# 1_P1.net
KiCad netlist of a schematic drawn in Altium Designer
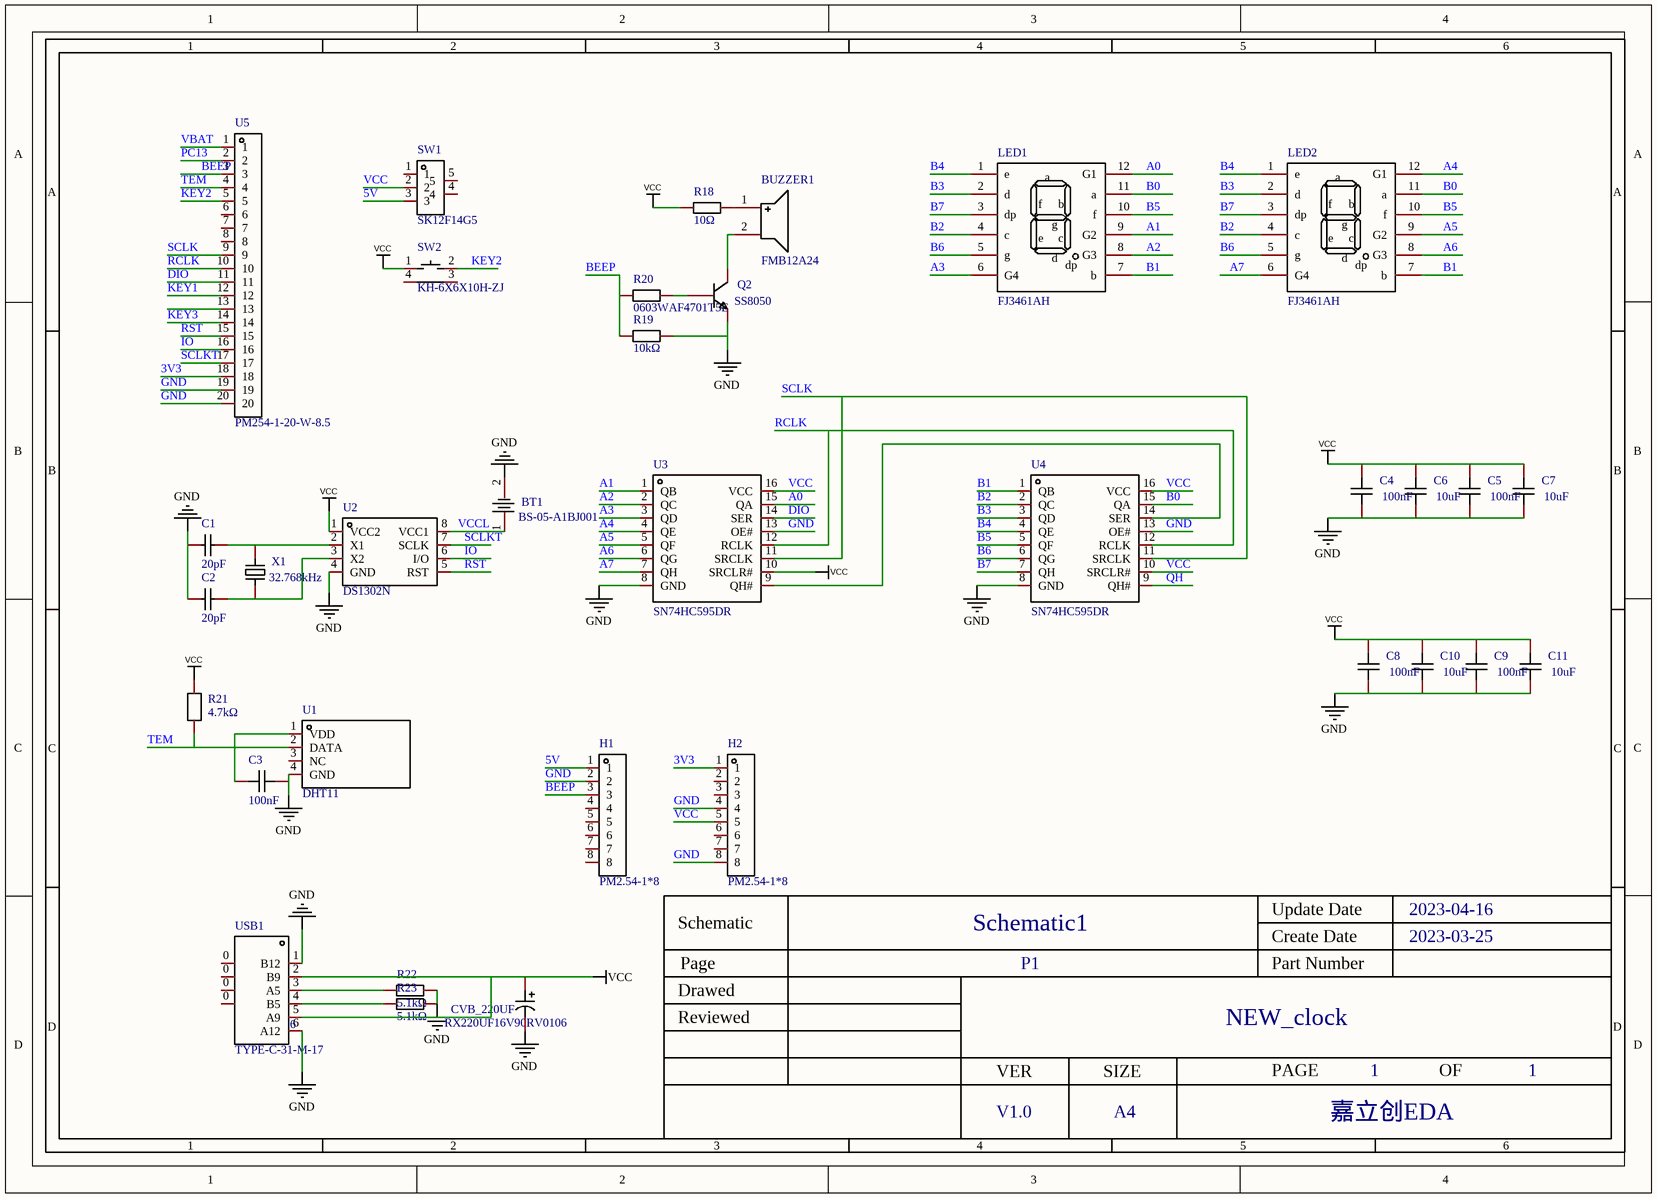
[diagram p0: 1_P1.schdoc]

(export (version "E")
  (design (tool "Eeschema 10.0.6"))
  (components
    (comp (ref "BT1")
      (value "BS-05-A1BJ001")
      (description "连接器类型:电池底座;适用电池规格:CR2032;工作温度范围:-25℃~+85℃;")
      (fields (field (name "NAME") "BS-05-A1BJ001") (field (name "MANUFACTURER") "MYOUNG(美阳)"))
      (libsource (lib "altium-import") (part "root_1_BS-05-A1BJ001_"))
    )
    (comp (ref "BUZZER1")
      (value "FMB12A24")
      (fields (field (name "NAME") "FMB12A24") (field (name "MANUFACTURER") "FUET(福声科技)"))
      (libsource (lib "altium-import") (part "root_0_FMB12A24_"))
    )
    (comp (ref "C1")
      (value "20pF")
      (description "容值:20pF;精度:±5%;额定电压:50V;材质(温度系数):C0G;")
      (fields
        (field (name "NAME") "20pF")
        (field (name "MANUFACTURER") "SAMSUNG(三星)")
        (field (name "MANUFACTURER PART") "CL10C200JB8NNNC")
      )
      (libsource (lib "altium-import") (part "root_0_CL10C200JB8NNNC_"))
    )
    (comp (ref "C2")
      (value "20pF")
      (description "容值:20pF;精度:±5%;额定电压:50V;材质(温度系数):C0G;")
      (fields
        (field (name "NAME") "20pF")
        (field (name "MANUFACTURER") "SAMSUNG(三星)")
        (field (name "MANUFACTURER PART") "CL10C200JB8NNNC")
      )
      (libsource (lib "altium-import") (part "root_0_CL10C200JB8NNNC_"))
    )
    (comp (ref "C3")
      (value "100nF")
      (description "容值:100nF;精度:±10%;额定电压:50V;材质(温度系数):X7R;")
      (fields
        (field (name "NAME") "100nF")
        (field (name "MANUFACTURER") "SAMSUNG(三星)")
        (field (name "MANUFACTURER PART") "CL10B104KB8NNNC")
      )
      (libsource (lib "altium-import") (part "root_0_CL10B104KB8NNNC_"))
    )
    (comp (ref "C4")
      (value "100nF")
      (description "容值:100nF;精度:±10%;额定电压:50V;材质(温度系数):X7R;")
      (fields
        (field (name "NAME") "100nF")
        (field (name "MANUFACTURER") "SAMSUNG(三星)")
        (field (name "MANUFACTURER PART") "CL10B104KB8NNNC")
      )
      (libsource (lib "altium-import") (part "root_1_CL10B104KB8NNNC_"))
    )
    (comp (ref "C5")
      (value "100nF")
      (description "容值:100nF;精度:±10%;额定电压:50V;材质(温度系数):X7R;")
      (fields
        (field (name "NAME") "100nF")
        (field (name "MANUFACTURER") "SAMSUNG(三星)")
        (field (name "MANUFACTURER PART") "CL10B104KB8NNNC")
      )
      (libsource (lib "altium-import") (part "root_1_CL10B104KB8NNNC_"))
    )
    (comp (ref "C6")
      (value "10uF")
      (description "容值:10uF;精度:±20%;额定电压:25V;材质(温度系数):X5R;")
      (fields
        (field (name "NAME") "10uF")
        (field (name "MANUFACTURER") "SAMSUNG(三星)")
        (field (name "MANUFACTURER PART") "CL10A106MA8NRNC")
      )
      (libsource (lib "altium-import") (part "root_1_CL10A106MA8NRNC_"))
    )
    (comp (ref "C7")
      (value "10uF")
      (description "容值:10uF;精度:±20%;额定电压:25V;材质(温度系数):X5R;")
      (fields
        (field (name "NAME") "10uF")
        (field (name "MANUFACTURER") "SAMSUNG(三星)")
        (field (name "MANUFACTURER PART") "CL10A106MA8NRNC")
      )
      (libsource (lib "altium-import") (part "root_1_CL10A106MA8NRNC_"))
    )
    (comp (ref "C8")
      (value "100nF")
      (description "容值:100nF;精度:±10%;额定电压:50V;材质(温度系数):X7R;")
      (fields
        (field (name "NAME") "100nF")
        (field (name "MANUFACTURER") "SAMSUNG(三星)")
        (field (name "MANUFACTURER PART") "CL10B104KB8NNNC")
      )
      (libsource (lib "altium-import") (part "root_1_CL10B104KB8NNNC_"))
    )
    (comp (ref "C9")
      (value "100nF")
      (description "容值:100nF;精度:±10%;额定电压:50V;材质(温度系数):X7R;")
      (fields
        (field (name "NAME") "100nF")
        (field (name "MANUFACTURER") "SAMSUNG(三星)")
        (field (name "MANUFACTURER PART") "CL10B104KB8NNNC")
      )
      (libsource (lib "altium-import") (part "root_1_CL10B104KB8NNNC_"))
    )
    (comp (ref "C10")
      (value "10uF")
      (description "容值:10uF;精度:±20%;额定电压:25V;材质(温度系数):X5R;")
      (fields
        (field (name "NAME") "10uF")
        (field (name "MANUFACTURER") "SAMSUNG(三星)")
        (field (name "MANUFACTURER PART") "CL10A106MA8NRNC")
      )
      (libsource (lib "altium-import") (part "root_1_CL10A106MA8NRNC_"))
    )
    (comp (ref "C11")
      (value "10uF")
      (description "容值:10uF;精度:±20%;额定电压:25V;材质(温度系数):X5R;")
      (fields
        (field (name "NAME") "10uF")
        (field (name "MANUFACTURER") "SAMSUNG(三星)")
        (field (name "MANUFACTURER PART") "CL10A106MA8NRNC")
      )
      (libsource (lib "altium-import") (part "root_1_CL10A106MA8NRNC_"))
    )
    (comp (ref "CVB_220UF")
      (value "RX220UF16V90RV0106")
      (description "RX系列小型化极低阻抗系列贴片电解电容器 105℃2000小时")
      (fields (field (name "NAME") "RX220UF16V90RV0106") (field (name "MANUFACTURER") "KNSCHA(科尼盛)"))
      (libsource (lib "altium-import") (part "root_3_RX220UF16V90RV0106_"))
    )
    (comp (ref "H1")
      (value "PM2.54-1*8")
      (fields (field (name "NAME") "PM2.54-1*8") (field (name "MANUFACTURER") "ZHOURI(洲日)"))
      (libsource (lib "altium-import") (part "root_0_PM2.54-1*8_"))
    )
    (comp (ref "H2")
      (value "PM2.54-1*8")
      (fields (field (name "NAME") "PM2.54-1*8") (field (name "MANUFACTURER") "ZHOURI(洲日)"))
      (libsource (lib "altium-import") (part "root_0_PM2.54-1*8_"))
    )
    (comp (ref "LED1")
      (value "FJ3461AH")
      (description "数字/字母大小(英寸):0.36;发光颜色:红色;")
      (fields (field (name "NAME") "FJ3461AH") (field (name "MANUFACTURER") "志浩"))
      (libsource (lib "altium-import") (part "root_0_FJ3461AH_"))
    )
    (comp (ref "LED2")
      (value "FJ3461AH")
      (description "数字/字母大小(英寸):0.36;发光颜色:红色;")
      (fields (field (name "NAME") "FJ3461AH") (field (name "MANUFACTURER") "志浩"))
      (libsource (lib "altium-import") (part "root_0_FJ3461AH_"))
    )
    (comp (ref "Q2")
      (value "SS8050")
      (fields (field (name "NAME") "SS8050") (field (name "MANUFACTURER") "CJ(江苏长电/长晶)"))
      (libsource (lib "altium-import") (part "root_0_SS8050_C177739_"))
    )
    (comp (ref "R18")
      (value "10Ω")
      (description "电阻类型:厚膜电阻;阻值:10Ω;精度:±5%;功率:100mW;温度系数:±100ppm/℃;最大工作电压:75V;工作温度范围:-55℃~+155℃;")
      (fields
        (field (name "NAME") "10Ω")
        (field (name "MANUFACTURER") "RALEC(旺诠)")
        (field (name "MANUFACTURER PART") "RTT03100JTP")
      )
      (libsource (lib "altium-import") (part "root_0_RTT03100JTP_"))
    )
    (comp (ref "R19")
      (value "10kΩ")
      (description "电阻类型:厚膜电阻;阻值:10kΩ;精度:±1%;功率:100mW;温度系数:±100ppm/℃;最大工作电压:75V;工作温度范围:-55℃~+155℃;")
      (fields
        (field (name "NAME") "10kΩ")
        (field (name "MANUFACTURER") "UNI-ROYAL(厚声)")
        (field (name "MANUFACTURER PART") "0603WAF1002T5E")
      )
      (libsource (lib "altium-import") (part "root_0_0603WAF1002T5E_"))
    )
    (comp (ref "R20")
      (value "0603WAF4701T5E")
      (fields (field (name "NAME") "0603WAF4701T5E") (field (name "MANUFACTURER") "UNI-ROYAL(厚声)"))
      (libsource (lib "altium-import") (part "root_0_0603WAF4701T5E_"))
    )
    (comp (ref "R21")
      (value "4.7kΩ")
      (description "电阻类型:厚膜电阻;阻值:4.7kΩ;精度:±5%;功率:100mW;温度系数:±200ppm/℃;最大工作电压:-;工作温度范围:-55℃~+155℃;")
      (fields
        (field (name "NAME") "4.7kΩ")
        (field (name "MANUFACTURER") "PANASONIC(松下)")
        (field (name "MANUFACTURER PART") "ERJ3GEYJ472V")
      )
      (libsource (lib "altium-import") (part "root_1_ERJ3GEYJ472V_"))
    )
    (comp (ref "R22")
      (value "5.1kΩ")
      (description "电阻类型:厚膜电阻;阻值:5.1kΩ;精度:±1%;功率:100mW;温度系数:±100ppm/℃;最大工作电压:75V;工作温度范围:-55℃~+155℃;")
      (fields
        (field (name "NAME") "5.1kΩ")
        (field (name "MANUFACTURER") "UNI-ROYAL(厚声)")
        (field (name "MANUFACTURER PART") "0603WAF5101T5E")
      )
      (libsource (lib "altium-import") (part "root_0_0603WAF5101T5E_"))
    )
    (comp (ref "R23")
      (value "5.1kΩ")
      (description "电阻类型:厚膜电阻;阻值:5.1kΩ;精度:±1%;功率:100mW;温度系数:±100ppm/℃;最大工作电压:75V;工作温度范围:-55℃~+155℃;")
      (fields
        (field (name "NAME") "5.1kΩ")
        (field (name "MANUFACTURER") "UNI-ROYAL(厚声)")
        (field (name "MANUFACTURER PART") "0603WAF5101T5E")
      )
      (libsource (lib "altium-import") (part "root_0_0603WAF5101T5E_"))
    )
    (comp (ref "SW1")
      (value "SK12F14G5")
      (fields (field (name "NAME") "SK12F14G5") (field (name "MANUFACTURER") "SHOU HAN(首韩)"))
      (libsource (lib "altium-import") (part "root_0_SK12F14G5_"))
    )
    (comp (ref "SW2")
      (value "KH-6X6X10H-ZJ")
      (fields (field (name "NAME") "KH-6X6X10H-ZJ") (field (name "MANUFACTURER") "kinghelm(金航标)"))
      (libsource (lib "altium-import") (part "root_0_KH-6X6X10H-ZJ_"))
    )
    (comp (ref "U1")
      (value "DHT11")
      (description "新款电容式数字温湿度传感器,老款已停产16.1x12.6x5.8mm")
      (fields (field (name "NAME") "DHT11") (field (name "MANUFACTURER") "广州奥松"))
      (libsource (lib "altium-import") (part "root_0_DHT11_"))
    )
    (comp (ref "U2")
      (value "DS1302N")
      (fields (field (name "NAME") "DS1302N") (field (name "MANUFACTURER") "HGSEMI(华冠)"))
      (libsource (lib "altium-import") (part "root_0_DS1302N_"))
    )
    (comp (ref "U3")
      (value "SN74HC595DR")
      (description "逻辑电路的归属系列:74HC;逻辑类型:移位寄存器;输出类型:三态;功能:串行至并行, 串行;工作电压:2V~6V;")
      (fields (field (name "NAME") "SN74HC595DR") (field (name "MANUFACTURER") "TI(德州仪器)"))
      (libsource (lib "altium-import") (part "root_0_SN74HC595DR_"))
    )
    (comp (ref "U4")
      (value "SN74HC595DR")
      (description "逻辑电路的归属系列:74HC;逻辑类型:移位寄存器;输出类型:三态;功能:串行至并行, 串行;工作电压:2V~6V;")
      (fields (field (name "NAME") "SN74HC595DR") (field (name "MANUFACTURER") "TI(德州仪器)"))
      (libsource (lib "altium-import") (part "root_0_SN74HC595DR_"))
    )
    (comp (ref "U5")
      (value "PM254-1-20-W-8.5")
      (fields (field (name "NAME") "PM254-1-20-W-8.5") (field (name "MANUFACTURER") "HCTL(华灿天禄)"))
      (libsource (lib "altium-import") (part "root_0_PM254-1-20-W-8.5_"))
    )
    (comp (ref "USB1")
      (value "TYPE-C-31-M-17")
      (description "连接器类型:Type-C;标准:-;公母:母座;触点数量:6;端口数量:1;")
      (fields
        (field (name "NAME") "TYPE-C-31-M-17")
        (field (name "MANUFACTURER") "韩国韩荣")
        (field (name "NUMBER") "6")
      )
      (libsource (lib "altium-import") (part "root_0_TYPE-C-31-M-17_"))
    )
    (comp (ref "X1")
      (value "32.768kHz")
      (description "晶振类型:贴片无源晶振;频率:32.768kHz;频率公差:±20ppm;频率稳定度:-;负载电容:12.5pF;等效串联电阻(ESR):70kΩ;工作温度:-40℃~+85℃;")
      (fields
        (field (name "NAME") "32.768kHz")
        (field (name "MANUFACTURER") "EPSON(爱普生)")
        (field (name "MANUFACTURER PART") "FC-135 32.7680KA-A")
      )
      (libsource (lib "altium-import") (part "root_1_FC-135 32.7680KA-A_"))
    )
  )
  (nets
    (net (code "1") (name "/3V3") (class "Default")
      (node (ref "H2") (pin "1") (pinfunction "1_1") (pintype "passive"))
      (node (ref "U5") (pin "18") (pinfunction "18_18") (pintype "passive"))
    )
    (net (code "2") (name "/5V") (class "Default")
      (node (ref "H1") (pin "1") (pinfunction "1_1") (pintype "passive"))
      (node (ref "SW1") (pin "3") (pinfunction "3_3") (pintype "passive"))
    )
    (net (code "3") (name "/A0") (class "Default")
      (node (ref "LED1") (pin "12") (pinfunction "G1_12") (pintype "passive"))
      (node (ref "U3") (pin "15") (pinfunction "QA_15") (pintype "passive"))
    )
    (net (code "4") (name "/A1") (class "Default")
      (node (ref "LED1") (pin "9") (pinfunction "G2_9") (pintype "passive"))
      (node (ref "U3") (pin "1") (pinfunction "QB_1") (pintype "passive"))
    )
    (net (code "5") (name "/A2") (class "Default")
      (node (ref "LED1") (pin "8") (pinfunction "G3_8") (pintype "passive"))
      (node (ref "U3") (pin "2") (pinfunction "QC_2") (pintype "passive"))
    )
    (net (code "6") (name "/A3") (class "Default")
      (node (ref "LED1") (pin "6") (pinfunction "G4_6") (pintype "passive"))
      (node (ref "U3") (pin "3") (pinfunction "QD_3") (pintype "passive"))
    )
    (net (code "7") (name "/A4") (class "Default")
      (node (ref "LED2") (pin "12") (pinfunction "G1_12") (pintype "passive"))
      (node (ref "U3") (pin "4") (pinfunction "QE_4") (pintype "passive"))
    )
    (net (code "8") (name "/A5") (class "Default")
      (node (ref "LED2") (pin "9") (pinfunction "G2_9") (pintype "passive"))
      (node (ref "U3") (pin "5") (pinfunction "QF_5") (pintype "passive"))
    )
    (net (code "9") (name "/A6") (class "Default")
      (node (ref "LED2") (pin "8") (pinfunction "G3_8") (pintype "passive"))
      (node (ref "U3") (pin "6") (pinfunction "QG_6") (pintype "passive"))
    )
    (net (code "10") (name "/A7") (class "Default")
      (node (ref "LED2") (pin "6") (pinfunction "G4_6") (pintype "passive"))
      (node (ref "U3") (pin "7") (pinfunction "QH_7") (pintype "passive"))
    )
    (net (code "11") (name "/B0") (class "Default")
      (node (ref "LED1") (pin "11") (pinfunction "a_11") (pintype "passive"))
      (node (ref "LED2") (pin "11") (pinfunction "a_11") (pintype "passive"))
      (node (ref "U4") (pin "15") (pinfunction "QA_15") (pintype "passive"))
    )
    (net (code "12") (name "/B1") (class "Default")
      (node (ref "LED1") (pin "7") (pinfunction "b_7") (pintype "passive"))
      (node (ref "LED2") (pin "7") (pinfunction "b_7") (pintype "passive"))
      (node (ref "U4") (pin "1") (pinfunction "QB_1") (pintype "passive"))
    )
    (net (code "13") (name "/B2") (class "Default")
      (node (ref "LED1") (pin "4") (pinfunction "c_4") (pintype "passive"))
      (node (ref "LED2") (pin "4") (pinfunction "c_4") (pintype "passive"))
      (node (ref "U4") (pin "2") (pinfunction "QC_2") (pintype "passive"))
    )
    (net (code "14") (name "/B3") (class "Default")
      (node (ref "LED1") (pin "2") (pinfunction "d_2") (pintype "passive"))
      (node (ref "LED2") (pin "2") (pinfunction "d_2") (pintype "passive"))
      (node (ref "U4") (pin "3") (pinfunction "QD_3") (pintype "passive"))
    )
    (net (code "15") (name "/B4") (class "Default")
      (node (ref "LED1") (pin "1") (pinfunction "e_1") (pintype "passive"))
      (node (ref "LED2") (pin "1") (pinfunction "e_1") (pintype "passive"))
      (node (ref "U4") (pin "4") (pinfunction "QE_4") (pintype "passive"))
    )
    (net (code "16") (name "/B5") (class "Default")
      (node (ref "LED1") (pin "10") (pinfunction "f_10") (pintype "passive"))
      (node (ref "LED2") (pin "10") (pinfunction "f_10") (pintype "passive"))
      (node (ref "U4") (pin "5") (pinfunction "QF_5") (pintype "passive"))
    )
    (net (code "17") (name "/B6") (class "Default")
      (node (ref "LED1") (pin "5") (pinfunction "g_5") (pintype "passive"))
      (node (ref "LED2") (pin "5") (pinfunction "g_5") (pintype "passive"))
      (node (ref "U4") (pin "6") (pinfunction "QG_6") (pintype "passive"))
    )
    (net (code "18") (name "/B7") (class "Default")
      (node (ref "LED1") (pin "3") (pinfunction "dp_3") (pintype "passive"))
      (node (ref "LED2") (pin "3") (pinfunction "dp_3") (pintype "passive"))
      (node (ref "U4") (pin "7") (pinfunction "QH_7") (pintype "passive"))
    )
    (net (code "19") (name "/BEEP") (class "Default")
      (node (ref "H1") (pin "3") (pinfunction "3_3") (pintype "passive"))
      (node (ref "R19") (pin "1") (pinfunction "1_1") (pintype "passive"))
      (node (ref "R20") (pin "1") (pinfunction "1_1") (pintype "passive"))
      (node (ref "U5") (pin "3") (pinfunction "3_3") (pintype "passive"))
    )
    (net (code "20") (name "/DIO") (class "Default")
      (node (ref "U3") (pin "14") (pinfunction "SER_14") (pintype "passive"))
      (node (ref "U5") (pin "11") (pinfunction "11_11") (pintype "passive"))
    )
    (net (code "21") (name "/IO") (class "Default")
      (node (ref "U2") (pin "6") (pinfunction "I/O_6") (pintype "passive"))
      (node (ref "U5") (pin "16") (pinfunction "16_16") (pintype "passive"))
    )
    (net (code "22") (name "/KEY1") (class "Default")
      (node (ref "U5") (pin "12") (pinfunction "12_12") (pintype "passive"))
    )
    (net (code "23") (name "/KEY2") (class "Default")
      (node (ref "SW2") (pin "2") (pinfunction "2_2") (pintype "passive"))
      (node (ref "U5") (pin "5") (pinfunction "5_5") (pintype "passive"))
    )
    (net (code "24") (name "/KEY3") (class "Default")
      (node (ref "U5") (pin "14") (pinfunction "14_14") (pintype "passive"))
    )
    (net (code "25") (name "/PC13") (class "Default")
      (node (ref "U5") (pin "2") (pinfunction "2_2") (pintype "passive"))
    )
    (net (code "26") (name "/QH") (class "Default")
      (node (ref "U4") (pin "9") (pinfunction "QH#_9") (pintype "passive"))
    )
    (net (code "27") (name "/RCLK") (class "Default")
      (node (ref "U3") (pin "12") (pinfunction "RCLK_12") (pintype "passive"))
      (node (ref "U4") (pin "12") (pinfunction "RCLK_12") (pintype "passive"))
      (node (ref "U5") (pin "10") (pinfunction "10_10") (pintype "passive"))
    )
    (net (code "28") (name "/RST") (class "Default")
      (node (ref "U2") (pin "5") (pinfunction "RST_5") (pintype "passive"))
      (node (ref "U5") (pin "15") (pinfunction "15_15") (pintype "passive"))
    )
    (net (code "29") (name "/SCLK") (class "Default")
      (node (ref "U3") (pin "11") (pinfunction "SRCLK_11") (pintype "passive"))
      (node (ref "U4") (pin "11") (pinfunction "SRCLK_11") (pintype "passive"))
      (node (ref "U5") (pin "9") (pinfunction "9_9") (pintype "passive"))
    )
    (net (code "30") (name "/SCLKT") (class "Default")
      (node (ref "U2") (pin "7") (pinfunction "SCLK_7") (pintype "passive"))
      (node (ref "U5") (pin "17") (pinfunction "17_17") (pintype "passive"))
    )
    (net (code "31") (name "/TEM") (class "Default")
      (node (ref "R21") (pin "1") (pinfunction "1_1") (pintype "passive"))
      (node (ref "U1") (pin "2") (pinfunction "DATA_2") (pintype "passive"))
      (node (ref "U5") (pin "4") (pinfunction "4_4") (pintype "passive"))
    )
    (net (code "32") (name "/VBAT") (class "Default")
      (node (ref "U5") (pin "1") (pinfunction "1_1") (pintype "passive"))
    )
    (net (code "33") (name "/VCCL") (class "Default")
      (node (ref "BT1") (pin "1") (pinfunction "1_1") (pintype "passive"))
      (node (ref "U2") (pin "8") (pinfunction "VCC1_8") (pintype "passive"))
    )
    (net (code "34") (name "GND") (class "Default")
      (node (ref "BT1") (pin "2") (pinfunction "2_2") (pintype "passive"))
      (node (ref "C1") (pin "1") (pinfunction "1_1") (pintype "passive"))
      (node (ref "C10") (pin "1") (pinfunction "1_1") (pintype "passive"))
      (node (ref "C11") (pin "1") (pinfunction "1_1") (pintype "passive"))
      (node (ref "C2") (pin "1") (pinfunction "1_1") (pintype "passive"))
      (node (ref "C3") (pin "2") (pinfunction "2_2") (pintype "passive"))
      (node (ref "C4") (pin "1") (pinfunction "1_1") (pintype "passive"))
      (node (ref "C5") (pin "1") (pinfunction "1_1") (pintype "passive"))
      (node (ref "C6") (pin "1") (pinfunction "1_1") (pintype "passive"))
      (node (ref "C7") (pin "1") (pinfunction "1_1") (pintype "passive"))
      (node (ref "C8") (pin "1") (pinfunction "1_1") (pintype "passive"))
      (node (ref "C9") (pin "1") (pinfunction "1_1") (pintype "passive"))
      (node (ref "CVB_220UF") (pin "2") (pinfunction "2_2") (pintype "passive"))
      (node (ref "H1") (pin "2") (pinfunction "2_2") (pintype "passive"))
      (node (ref "H2") (pin "4") (pinfunction "4_4") (pintype "passive"))
      (node (ref "H2") (pin "8") (pinfunction "8_8") (pintype "passive"))
      (node (ref "Q2") (pin "2") (pinfunction "E_2") (pintype "passive"))
      (node (ref "R19") (pin "2") (pinfunction "2_2") (pintype "passive"))
      (node (ref "R22") (pin "2") (pinfunction "2_2") (pintype "passive"))
      (node (ref "R23") (pin "2") (pinfunction "2_2") (pintype "passive"))
      (node (ref "U1") (pin "4") (pinfunction "GND_4") (pintype "passive"))
      (node (ref "U2") (pin "4") (pinfunction "GND_4") (pintype "passive"))
      (node (ref "U3") (pin "13") (pinfunction "OE#_13") (pintype "passive"))
      (node (ref "U3") (pin "8") (pinfunction "GND_8") (pintype "passive"))
      (node (ref "U4") (pin "13") (pinfunction "OE#_13") (pintype "passive"))
      (node (ref "U4") (pin "8") (pinfunction "GND_8") (pintype "passive"))
      (node (ref "U5") (pin "19") (pinfunction "19_19") (pintype "passive"))
      (node (ref "U5") (pin "20") (pinfunction "20_20") (pintype "passive"))
      (node (ref "USB1") (pin "1") (pinfunction "B12_1") (pintype "passive"))
      (node (ref "USB1") (pin "6") (pinfunction "A12_6") (pintype "passive"))
    )
    (net (code "35") (name "Net-(BUZZER1-Pad1)") (class "Default")
      (node (ref "BUZZER1") (pin "1") (pinfunction "1_1") (pintype "passive"))
      (node (ref "R18") (pin "2") (pinfunction "2_2") (pintype "passive"))
    )
    (net (code "36") (name "Net-(Q2-B)") (class "Default")
      (node (ref "Q2") (pin "1") (pinfunction "B_1") (pintype "passive"))
      (node (ref "R20") (pin "2") (pinfunction "2_2") (pintype "passive"))
    )
    (net (code "37") (name "Net-(Q2-C)") (class "Default")
      (node (ref "BUZZER1") (pin "2") (pinfunction "2_2") (pintype "passive"))
      (node (ref "Q2") (pin "3") (pinfunction "C_3") (pintype "passive"))
    )
    (net (code "38") (name "Net-(U1-VDD)") (class "Default")
      (node (ref "C3") (pin "1") (pinfunction "1_1") (pintype "passive"))
      (node (ref "U1") (pin "1") (pinfunction "VDD_1") (pintype "passive"))
    )
    (net (code "39") (name "Net-(U2-X1)") (class "Default")
      (node (ref "C1") (pin "2") (pinfunction "2_2") (pintype "passive"))
      (node (ref "U2") (pin "2") (pinfunction "X1_2") (pintype "passive"))
      (node (ref "X1") (pin "2") (pinfunction "2_2") (pintype "passive"))
    )
    (net (code "40") (name "Net-(U2-X2)") (class "Default")
      (node (ref "C2") (pin "2") (pinfunction "2_2") (pintype "passive"))
      (node (ref "U2") (pin "3") (pinfunction "X2_3") (pintype "passive"))
      (node (ref "X1") (pin "1") (pinfunction "1_1") (pintype "passive"))
    )
    (net (code "41") (name "Net-(U3-QH#)") (class "Default")
      (node (ref "U3") (pin "9") (pinfunction "QH#_9") (pintype "passive"))
      (node (ref "U4") (pin "14") (pinfunction "SER_14") (pintype "passive"))
    )
    (net (code "42") (name "Net-(USB1-A5)") (class "Default")
      (node (ref "R22") (pin "1") (pinfunction "1_1") (pintype "passive"))
      (node (ref "USB1") (pin "3") (pinfunction "A5_3") (pintype "passive"))
    )
    (net (code "43") (name "Net-(USB1-B5)") (class "Default")
      (node (ref "R23") (pin "1") (pinfunction "1_1") (pintype "passive"))
      (node (ref "USB1") (pin "4") (pinfunction "B5_4") (pintype "passive"))
    )
    (net (code "44") (name "VCC") (class "Default")
      (node (ref "C10") (pin "2") (pinfunction "2_2") (pintype "passive"))
      (node (ref "C11") (pin "2") (pinfunction "2_2") (pintype "passive"))
      (node (ref "C4") (pin "2") (pinfunction "2_2") (pintype "passive"))
      (node (ref "C5") (pin "2") (pinfunction "2_2") (pintype "passive"))
      (node (ref "C6") (pin "2") (pinfunction "2_2") (pintype "passive"))
      (node (ref "C7") (pin "2") (pinfunction "2_2") (pintype "passive"))
      (node (ref "C8") (pin "2") (pinfunction "2_2") (pintype "passive"))
      (node (ref "C9") (pin "2") (pinfunction "2_2") (pintype "passive"))
      (node (ref "CVB_220UF") (pin "1") (pinfunction "1_1") (pintype "passive"))
      (node (ref "H2") (pin "5") (pinfunction "5_5") (pintype "passive"))
      (node (ref "R18") (pin "1") (pinfunction "1_1") (pintype "passive"))
      (node (ref "R21") (pin "2") (pinfunction "2_2") (pintype "passive"))
      (node (ref "SW1") (pin "2") (pinfunction "2_2") (pintype "passive"))
      (node (ref "SW2") (pin "1") (pinfunction "1_1") (pintype "passive"))
      (node (ref "U2") (pin "1") (pinfunction "VCC2_1") (pintype "passive"))
      (node (ref "U3") (pin "10") (pinfunction "SRCLR#_10") (pintype "passive"))
      (node (ref "U3") (pin "16") (pinfunction "VCC_16") (pintype "passive"))
      (node (ref "U4") (pin "10") (pinfunction "SRCLR#_10") (pintype "passive"))
      (node (ref "U4") (pin "16") (pinfunction "VCC_16") (pintype "passive"))
      (node (ref "USB1") (pin "2") (pinfunction "B9_2") (pintype "passive"))
      (node (ref "USB1") (pin "5") (pinfunction "A9_5") (pintype "passive"))
    )
    (net (code "45") (name "unconnected-(H1-Pad4)") (class "Default")
      (node (ref "H1") (pin "4") (pinfunction "4_4") (pintype "passive"))
    )
    (net (code "46") (name "unconnected-(H1-Pad5)") (class "Default")
      (node (ref "H1") (pin "5") (pinfunction "5_5") (pintype "passive"))
    )
    (net (code "47") (name "unconnected-(H1-Pad6)") (class "Default")
      (node (ref "H1") (pin "6") (pinfunction "6_6") (pintype "passive"))
    )
    (net (code "48") (name "unconnected-(H1-Pad7)") (class "Default")
      (node (ref "H1") (pin "7") (pinfunction "7_7") (pintype "passive"))
    )
    (net (code "49") (name "unconnected-(H1-Pad8)") (class "Default")
      (node (ref "H1") (pin "8") (pinfunction "8_8") (pintype "passive"))
    )
    (net (code "50") (name "unconnected-(H2-Pad2)") (class "Default")
      (node (ref "H2") (pin "2") (pinfunction "2_2") (pintype "passive"))
    )
    (net (code "51") (name "unconnected-(H2-Pad3)") (class "Default")
      (node (ref "H2") (pin "3") (pinfunction "3_3") (pintype "passive"))
    )
    (net (code "52") (name "unconnected-(H2-Pad6)") (class "Default")
      (node (ref "H2") (pin "6") (pinfunction "6_6") (pintype "passive"))
    )
    (net (code "53") (name "unconnected-(H2-Pad7)") (class "Default")
      (node (ref "H2") (pin "7") (pinfunction "7_7") (pintype "passive"))
    )
    (net (code "54") (name "unconnected-(SW1-Pad1)") (class "Default")
      (node (ref "SW1") (pin "1") (pinfunction "1_1") (pintype "passive"))
    )
    (net (code "55") (name "unconnected-(SW1-Pad4)") (class "Default")
      (node (ref "SW1") (pin "4") (pinfunction "4_4") (pintype "passive"))
    )
    (net (code "56") (name "unconnected-(SW1-Pad5)") (class "Default")
      (node (ref "SW1") (pin "5") (pinfunction "5_5") (pintype "passive"))
    )
    (net (code "57") (name "unconnected-(SW2-Pad3)") (class "Default")
      (node (ref "SW2") (pin "3") (pinfunction "3_3") (pintype "passive"))
    )
    (net (code "58") (name "unconnected-(SW2-Pad4)") (class "Default")
      (node (ref "SW2") (pin "4") (pinfunction "4_4") (pintype "passive"))
    )
    (net (code "59") (name "unconnected-(U1-NC-Pad3)") (class "Default")
      (node (ref "U1") (pin "3") (pinfunction "NC_3") (pintype "passive"))
    )
    (net (code "60") (name "unconnected-(U5-Pad6)") (class "Default")
      (node (ref "U5") (pin "6") (pinfunction "6_6") (pintype "passive"))
    )
    (net (code "61") (name "unconnected-(U5-Pad7)") (class "Default")
      (node (ref "U5") (pin "7") (pinfunction "7_7") (pintype "passive"))
    )
    (net (code "62") (name "unconnected-(U5-Pad8)") (class "Default")
      (node (ref "U5") (pin "8") (pinfunction "8_8") (pintype "passive"))
    )
    (net (code "63") (name "unconnected-(U5-Pad13)") (class "Default")
      (node (ref "U5") (pin "13") (pinfunction "13_13") (pintype "passive"))
    )
    (net (code "64") (name "unconnected-(USB1-Pad0)") (class "Default")
      (node (ref "USB1") (pin "0") (pinfunction "0_0") (pintype "passive"))
    )
    (net (code "65") (name "unconnected-(USB1-Pad0)_1") (class "Default")
      (node (ref "USB1") (pin "0") (pinfunction "0_0") (pintype "passive"))
    )
    (net (code "66") (name "unconnected-(USB1-Pad0)_2") (class "Default")
      (node (ref "USB1") (pin "0") (pinfunction "0_0") (pintype "passive"))
    )
    (net (code "67") (name "unconnected-(USB1-Pad0)_3") (class "Default")
      (node (ref "USB1") (pin "0") (pinfunction "0_0") (pintype "passive"))
    )
  )
)
